# 8MHz_Crystal.net
KiCad netlist of a schematic drawn in Altium Designer
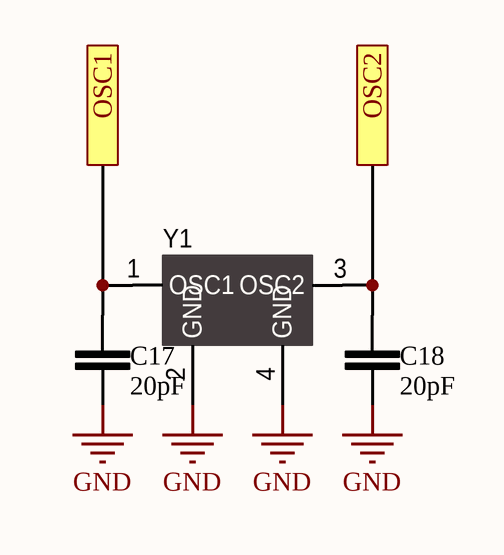
[diagram p0: 8MHz_Crystal.SchDoc]

(export (version "E")
  (design (tool "Eeschema 10.0.6"))
  (components
    (comp (ref "C17")
      (value "20pF")
      (footprint "CER_0603")
      (description "CAP CER 20p 0805")
      (libsource (lib "Capacitors") (part "00002200"))
    )
    (comp (ref "C18")
      (value "20pF")
      (footprint "CER_0603")
      (description "CAP CER 20p 0805")
      (libsource (lib "Capacitors") (part "00002200"))
    )
    (comp (ref "Y1")
      (value "8Hz")
      (footprint "ABM10")
      (description "CRYSTAL 8.0000MHZ 18PF SMD")
      (fields
        (field (name "MANUFACTURER") "ABRACON")
        (field (name "MANUFACTURER PART NUMBER") "ABMM2-8.000MHZ-E2-T")
      )
      (libsource (lib "Discrete_Semiconductor") (part "QUARTZ_8MHz"))
    )
  )
  (nets
    (net (code "1") (name "/OSC1") (class "Default")
      (node (ref "C17") (pin "2") (pinfunction "2_2") (pintype "passive"))
      (node (ref "Y1") (pin "1") (pinfunction "OSC1_1") (pintype "passive"))
    )
    (net (code "2") (name "/OSC2") (class "Default")
      (node (ref "C18") (pin "2") (pinfunction "2_2") (pintype "passive"))
      (node (ref "Y1") (pin "3") (pinfunction "OSC2_3") (pintype "passive"))
    )
    (net (code "3") (name "GND") (class "Default")
      (node (ref "C17") (pin "1") (pinfunction "1_1") (pintype "passive"))
      (node (ref "C18") (pin "1") (pinfunction "1_1") (pintype "passive"))
      (node (ref "Y1") (pin "2") (pinfunction "GND_2") (pintype "passive"))
      (node (ref "Y1") (pin "4") (pinfunction "GND_4") (pintype "passive"))
    )
  )
)
